# EStop.net
KiCad netlist of a schematic drawn in Altium Designer
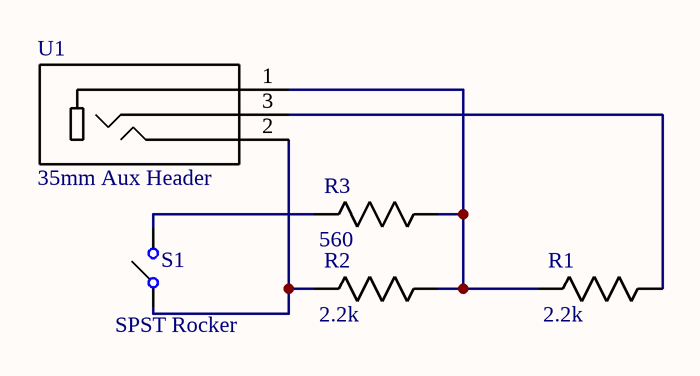
[diagram p0: EStop.SchDoc]

(export (version "E")
  (design (tool "Eeschema 10.0.6"))
  (components
    (comp (ref "R1")
      (value "2.2k")
      (footprint "RESC2013X65N")
      (description "RES SMD 2.2K OHM 1% 1/8W 0805")
      (fields (field (name "MP") "RC0805FR-072K2L") (field (name "MF") "Yageo"))
      (libsource (lib "AltiumLibraries") (part "RES 2.2k 0805"))
    )
    (comp (ref "R2")
      (value "2.2k")
      (footprint "RESC2013X65N")
      (description "RES SMD 2.2K OHM 1% 1/8W 0805")
      (fields (field (name "MP") "RC0805FR-072K2L") (field (name "MF") "Yageo"))
      (libsource (lib "AltiumLibraries") (part "RES 2.2k 0805"))
    )
    (comp (ref "R3")
      (value "560")
      (footprint "RESC2013X65N")
      (description "RES 560 OHM 1% 1/8W 0805")
      (fields (field (name "MP") "RMCF0805FT560R") (field (name "MF") "Stackpole Electronics Inc"))
      (libsource (lib "AltiumLibraries") (part "RES 560 0805"))
    )
    (comp (ref "S1")
      (value "SPST Rocker")
      (footprint "SWITCH ROCKER SPST 10A 125V")
      (description "Rocker Switch SPST 10A (AC) 125V Panel Mount, Snap-In")
      (fields (field (name "MP") "SRB22A2FBBNN") (field (name "MF") "ZF Electronics"))
      (libsource (lib "AltiumLibraries") (part "SWITCH ROCKER SPST 10A 125V"))
    )
    (comp (ref "U1")
      (value "35mm Aux Header")
      (footprint "35mm Aux Header")
      (libsource (lib "AltiumLibraries") (part "35mm Aux Header"))
    )
  )
  (nets
    (net (code "1") (name "Net-(R1-R1)") (class "Default")
      (node (ref "R1") (pin "1") (pinfunction "R1_1") (pintype "passive"))
      (node (ref "U1") (pin "3") (pinfunction "3_3") (pintype "passive"))
    )
    (net (code "2") (name "Net-(R1-R2)") (class "Default")
      (node (ref "R1") (pin "2") (pinfunction "R2_2") (pintype "passive"))
      (node (ref "R2") (pin "1") (pinfunction "R1_1") (pintype "passive"))
      (node (ref "R3") (pin "1") (pinfunction "R1_1") (pintype "passive"))
      (node (ref "U1") (pin "1") (pinfunction "1_1") (pintype "passive"))
    )
    (net (code "3") (name "Net-(R2-R2)") (class "Default")
      (node (ref "R2") (pin "2") (pinfunction "R2_2") (pintype "passive"))
      (node (ref "S1") (pin "0") (pinfunction "0_0") (pintype "passive"))
      (node (ref "U1") (pin "2") (pinfunction "2_2") (pintype "passive"))
    )
    (net (code "4") (name "Net-(R3-R2)") (class "Default")
      (node (ref "R3") (pin "2") (pinfunction "R2_2") (pintype "passive"))
      (node (ref "S1") (pin "1") (pinfunction "1_1") (pintype "passive"))
    )
  )
)
